# mcu.net
KiCad netlist of a schematic drawn in Altium Designer
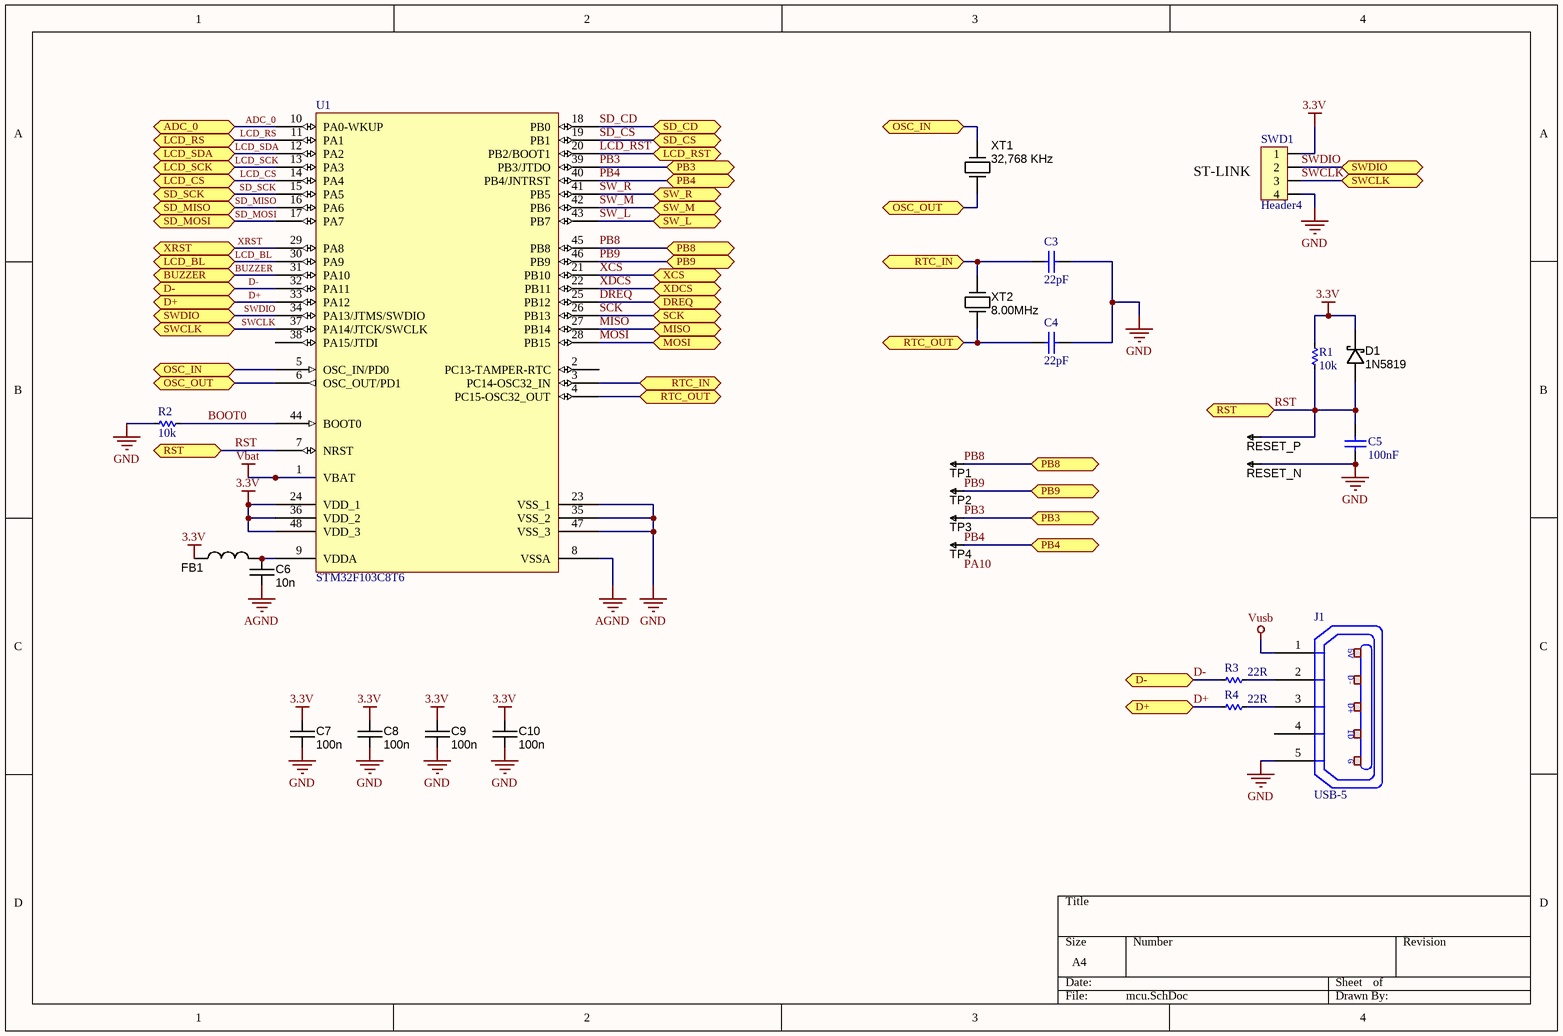
[diagram p0: mcu.SchDoc]

(export (version "E")
  (design (tool "Eeschema 10.0.6"))
  (components
    (comp (ref "C3")
      (value "22pF")
      (footprint "C0805")
      (description "Capacitor (Semiconductor SIM Model)")
      (fields (field (name "Comment") "Cap Semi") (field (name "PUBLISHER") "Altium Limited"))
      (libsource (lib "Mylib") (part "Cap Semi"))
    )
    (comp (ref "C4")
      (value "22pF")
      (footprint "C0805")
      (description "Capacitor (Semiconductor SIM Model)")
      (fields (field (name "Comment") "Cap Semi") (field (name "PUBLISHER") "Altium Limited"))
      (libsource (lib "Mylib") (part "Cap Semi"))
    )
    (comp (ref "C5")
      (value "100nF")
      (footprint "C0805")
      (description "Capacitor (Semiconductor SIM Model)")
      (fields (field (name "Comment") "Cap Semi") (field (name "PUBLISHER") "Altium Limited"))
      (libsource (lib "Mylib") (part "Cap Semi"))
    )
    (comp (ref "C6")
      (value "10n")
      (footprint "CAPC1608X90N")
      (description "Capacitor SMD Cer 100nF 10% 50V X7R 0603")
      (fields (field (name "TOLERANCE") "±10%") (field (name "Comment") "approved sub OK"))
      (libsource (lib "PBL - Capacitors") (part "CAPC_100n_0603_X7R_50V_10%"))
    )
    (comp (ref "C7")
      (value "100n")
      (footprint "CAPC1608X90N")
      (description "Capacitor SMD Cer 100nF 10% 50V X7R 0603")
      (fields (field (name "TOLERANCE") "±10%") (field (name "Comment") "approved sub OK"))
      (libsource (lib "PBL - Capacitors") (part "CAPC_100n_0603_X7R_50V_10%"))
    )
    (comp (ref "C8")
      (value "100n")
      (footprint "CAPC1608X90N")
      (description "Capacitor SMD Cer 100nF 10% 50V X7R 0603")
      (fields (field (name "TOLERANCE") "±10%") (field (name "Comment") "approved sub OK"))
      (libsource (lib "PBL - Capacitors") (part "CAPC_100n_0603_X7R_50V_10%"))
    )
    (comp (ref "C9")
      (value "100n")
      (footprint "CAPC1608X90N")
      (description "Capacitor SMD Cer 100nF 10% 50V X7R 0603")
      (fields (field (name "TOLERANCE") "±10%") (field (name "Comment") "approved sub OK"))
      (libsource (lib "PBL - Capacitors") (part "CAPC_100n_0603_X7R_50V_10%"))
    )
    (comp (ref "C10")
      (value "100n")
      (footprint "CAPC1608X90N")
      (description "Capacitor SMD Cer 100nF 10% 50V X7R 0603")
      (fields (field (name "TOLERANCE") "±10%") (field (name "Comment") "approved sub OK"))
      (libsource (lib "PBL - Capacitors") (part "CAPC_100n_0603_X7R_50V_10%"))
    )
    (comp (ref "D1")
      (value "DIODE_SCHOTTKY_40V_1A")
      (footprint "SOD123")
      (description "Diode Schottky SMD 40V 1A SOD123")
      (fields (field (name "MANUFACTURER PART NUMBER 1") "1N5819"))
      (libsource (lib "PBL - Diodes") (part "DIODE_SCHOTTKY_40V_1A"))
    )
    (comp (ref "FB1")
      (value "2K2 @ 100 MHz")
      (footprint "FBC2012N")
      (description "Ferrite bead 2.2K Ohm at 100 MHz 200mA 0805 SMD")
      (libsource (lib "PBL - Inductors") (part "FERRITE_2K2-100MHz_0805"))
    )
    (comp (ref "J1")
      (value "USB-5")
      (footprint "USB-M1")
      (fields
        (field (name "MANUFACTURER") "FCI")
        (field (name "MANUFACTURER PART NUMBER") "10118193-0001LF")
        (field (name ".CREATOR") "MM")
        (field (name ".CHECKED PCB") "RF")
        (field (name ".CHECKED SCH") "MM")
      )
      (libsource (lib "LIBRARY") (part "USB-5"))
    )
    (comp (ref "R1")
      (value "10k")
      (footprint "RES-SMD-0805")
      (description "Resistor")
      (fields
        (field (name "MANUFACTURER") "Generic Components")
        (field (name "Comment") "Res")
        (field (name "PUBLISHER") "Altium Hobart Technology Centre")
      )
      (libsource (lib "Mylib") (part "Res-SMD"))
    )
    (comp (ref "R2")
      (value "10k")
      (footprint "RES-SMD-0603")
      (description "Resistor")
      (fields
        (field (name "MANUFACTURER") "Generic Components")
        (field (name "Comment") "Res")
        (field (name "PUBLISHER") "Altium Hobart Technology Centre")
      )
      (libsource (lib "Mylib") (part "Res-SMD"))
    )
    (comp (ref "R3")
      (value "22R")
      (footprint "RES-SMD-0603")
      (description "Resistor")
      (fields
        (field (name "MANUFACTURER") "Generic Components")
        (field (name "Comment") "Res")
        (field (name "PUBLISHER") "Altium Hobart Technology Centre")
      )
      (libsource (lib "Mylib") (part "Res-SMD"))
    )
    (comp (ref "R4")
      (value "22R")
      (footprint "RES-SMD-0603")
      (description "Resistor")
      (fields
        (field (name "MANUFACTURER") "Generic Components")
        (field (name "Comment") "Res")
        (field (name "PUBLISHER") "Altium Hobart Technology Centre")
      )
      (libsource (lib "Mylib") (part "Res-SMD"))
    )
    (comp (ref "RESET_N")
      (value "TESTPOINT")
      (footprint "TP-R60")
      (description "SMD test pin")
      (libsource (lib "PBL - Test Points") (part "TESTPOINT"))
    )
    (comp (ref "RESET_P")
      (value "TESTPOINT")
      (footprint "TP-R60")
      (description "SMD test pin")
      (libsource (lib "PBL - Test Points") (part "TESTPOINT"))
    )
    (comp (ref "SWD1")
      (value "Header4")
      (footprint "HDR4")
      (description "Header IDC, 4 x 1 Pin Vertical 2.54mm Pitch (Non-Boxed, Male)")
      (fields
        (field (name "MANUFACTURER") "Würth Elektronik eiSos GmbH")
        (field (name "PARTNO") "613002143121")
        (field (name "CREATED BY") "Karrer Zheng")
      )
      (libsource (lib "LIBRARY") (part "Header4"))
    )
    (comp (ref "TP1")
      (value "TESTPOINT")
      (footprint "TP-R60")
      (description "SMD test pin")
      (libsource (lib "PBL - Test Points") (part "TESTPOINT"))
    )
    (comp (ref "TP2")
      (value "TESTPOINT")
      (footprint "TP-R60")
      (description "SMD test pin")
      (libsource (lib "PBL - Test Points") (part "TESTPOINT"))
    )
    (comp (ref "TP3")
      (value "TESTPOINT")
      (footprint "TP-R60")
      (description "SMD test pin")
      (libsource (lib "PBL - Test Points") (part "TESTPOINT"))
    )
    (comp (ref "TP4")
      (value "TESTPOINT")
      (footprint "TP-R60")
      (description "SMD test pin")
      (libsource (lib "PBL - Test Points") (part "TESTPOINT"))
    )
    (comp (ref "U1")
      (value "STM32F103C8T6")
      (footprint "LQFP48_N")
      (description "STM32 ARM-based 32-bit MCU with 64 Kbytes Flash, 48-pin LQFP, Industrial Temperature")
      (fields (field (name "PUBLISHER") "Altium Limited"))
      (libsource (lib "ST Microcontroller 32-Bit STM32") (part "STM32F103C8T6"))
    )
    (comp (ref "XT1")
      (value "32,768 KHz")
      (footprint "CRYSTAL_CMR309T")
      (description "Resonator Ceramic 6.00 MHz 30ppm")
      (fields (field (name "TOLERANCE") "±50ppm"))
      (libsource (lib "PBL - Resonators") (part "Crystal_6MHz_CMR309T"))
    )
    (comp (ref "XT2")
      (value "8.00MHz")
      (footprint "CRYSTAL_HC49-US-SM")
      (description "Resonator Ceramic 6.00 MHz 30ppm")
      (libsource (lib "PBL - Resonators") (part "Crystal_6MHz_HC49/US"))
    )
  )
  (nets
    (net (code "1") (name "/ADC_0") (class "Default")
      (node (ref "U1") (pin "10") (pinfunction "PA0-WKUP_10") (pintype "bidirectional"))
    )
    (net (code "2") (name "/BOOT0") (class "Default")
      (node (ref "R2") (pin "1") (pinfunction "1_1") (pintype "passive"))
      (node (ref "U1") (pin "44") (pinfunction "BOOT0_44") (pintype "input"))
    )
    (net (code "3") (name "/BUZZER") (class "Default")
      (node (ref "U1") (pin "31") (pinfunction "PA10_31") (pintype "bidirectional"))
    )
    (net (code "4") (name "/D+") (class "Default")
      (node (ref "R4") (pin "2") (pinfunction "2_2") (pintype "passive"))
      (node (ref "U1") (pin "33") (pinfunction "PA12_33") (pintype "bidirectional"))
    )
    (net (code "5") (name "/D-") (class "Default")
      (node (ref "R3") (pin "2") (pinfunction "2_2") (pintype "passive"))
      (node (ref "U1") (pin "32") (pinfunction "PA11_32") (pintype "bidirectional"))
    )
    (net (code "6") (name "/DREQ") (class "Default")
      (node (ref "U1") (pin "25") (pinfunction "PB12_25") (pintype "bidirectional"))
    )
    (net (code "7") (name "/LCD_BL") (class "Default")
      (node (ref "U1") (pin "30") (pinfunction "PA9_30") (pintype "bidirectional"))
    )
    (net (code "8") (name "/LCD_CS") (class "Default")
      (node (ref "U1") (pin "14") (pinfunction "PA4_14") (pintype "bidirectional"))
    )
    (net (code "9") (name "/LCD_RS") (class "Default")
      (node (ref "U1") (pin "11") (pinfunction "PA1_11") (pintype "bidirectional"))
    )
    (net (code "10") (name "/LCD_RST") (class "Default")
      (node (ref "U1") (pin "20") (pinfunction "PB2/BOOT1_20") (pintype "bidirectional"))
    )
    (net (code "11") (name "/LCD_SCK") (class "Default")
      (node (ref "U1") (pin "13") (pinfunction "PA3_13") (pintype "bidirectional"))
    )
    (net (code "12") (name "/LCD_SDA") (class "Default")
      (node (ref "U1") (pin "12") (pinfunction "PA2_12") (pintype "bidirectional"))
    )
    (net (code "13") (name "/MISO") (class "Default")
      (node (ref "U1") (pin "27") (pinfunction "PB14_27") (pintype "bidirectional"))
    )
    (net (code "14") (name "/MOSI") (class "Default")
      (node (ref "U1") (pin "28") (pinfunction "PB15_28") (pintype "bidirectional"))
    )
    (net (code "15") (name "/OSC_IN") (class "Default")
      (node (ref "U1") (pin "5") (pinfunction "OSC_IN/PD0_5") (pintype "input"))
      (node (ref "XT1") (pin "2") (pinfunction "OUT_2") (pintype "passive"))
    )
    (net (code "16") (name "/OSC_OUT") (class "Default")
      (node (ref "U1") (pin "6") (pinfunction "OSC_OUT/PD1_6") (pintype "output"))
      (node (ref "XT1") (pin "1") (pinfunction "IN_1") (pintype "passive"))
    )
    (net (code "18") (name "/PB3") (class "Default")
      (node (ref "TP3") (pin "1") (pintype "passive"))
      (node (ref "U1") (pin "39") (pinfunction "PB3/JTDO_39") (pintype "bidirectional"))
    )
    (net (code "19") (name "/PB4") (class "Default")
      (node (ref "TP4") (pin "1") (pintype "passive"))
      (node (ref "U1") (pin "40") (pinfunction "PB4/JNTRST_40") (pintype "bidirectional"))
    )
    (net (code "20") (name "/PB8") (class "Default")
      (node (ref "TP1") (pin "1") (pintype "passive"))
      (node (ref "U1") (pin "45") (pinfunction "PB8_45") (pintype "bidirectional"))
    )
    (net (code "21") (name "/PB9") (class "Default")
      (node (ref "TP2") (pin "1") (pintype "passive"))
      (node (ref "U1") (pin "46") (pinfunction "PB9_46") (pintype "bidirectional"))
    )
    (net (code "22") (name "/RST") (class "Default")
      (node (ref "C5") (pin "2") (pinfunction "2_2") (pintype "passive"))
      (node (ref "D1") (pin "A") (pinfunction "A_A") (pintype "passive"))
      (node (ref "R1") (pin "2") (pinfunction "2_2") (pintype "passive"))
      (node (ref "RESET_P") (pin "1") (pintype "passive"))
      (node (ref "U1") (pin "7") (pinfunction "NRST_7") (pintype "bidirectional"))
    )
    (net (code "23") (name "/RTC_IN") (class "Default")
      (node (ref "C3") (pin "2") (pinfunction "2_2") (pintype "passive"))
      (node (ref "U1") (pin "3") (pinfunction "PC14-OSC32_IN_3") (pintype "bidirectional"))
      (node (ref "XT2") (pin "2") (pinfunction "OUT_2") (pintype "passive"))
    )
    (net (code "24") (name "/RTC_OUT") (class "Default")
      (node (ref "C4") (pin "2") (pinfunction "2_2") (pintype "passive"))
      (node (ref "U1") (pin "4") (pinfunction "PC15-OSC32_OUT_4") (pintype "bidirectional"))
      (node (ref "XT2") (pin "1") (pinfunction "IN_1") (pintype "passive"))
    )
    (net (code "25") (name "/SCK") (class "Default")
      (node (ref "U1") (pin "26") (pinfunction "PB13_26") (pintype "bidirectional"))
    )
    (net (code "26") (name "/SD_CD") (class "Default")
      (node (ref "U1") (pin "18") (pinfunction "PB0_18") (pintype "bidirectional"))
    )
    (net (code "27") (name "/SD_CS") (class "Default")
      (node (ref "U1") (pin "19") (pinfunction "PB1_19") (pintype "bidirectional"))
    )
    (net (code "28") (name "/SD_MISO") (class "Default")
      (node (ref "U1") (pin "16") (pinfunction "PA6_16") (pintype "bidirectional"))
    )
    (net (code "29") (name "/SD_MOSI") (class "Default")
      (node (ref "U1") (pin "17") (pinfunction "PA7_17") (pintype "bidirectional"))
    )
    (net (code "30") (name "/SD_SCK") (class "Default")
      (node (ref "U1") (pin "15") (pinfunction "PA5_15") (pintype "bidirectional"))
    )
    (net (code "31") (name "/SWCLK") (class "Default")
      (node (ref "SWD1") (pin "3") (pinfunction "3_3") (pintype "passive"))
      (node (ref "U1") (pin "37") (pinfunction "PA14/JTCK/SWCLK_37") (pintype "bidirectional"))
    )
    (net (code "32") (name "/SWDIO") (class "Default")
      (node (ref "SWD1") (pin "2") (pinfunction "2_2") (pintype "passive"))
      (node (ref "U1") (pin "34") (pinfunction "PA13/JTMS/SWDIO_34") (pintype "bidirectional"))
    )
    (net (code "33") (name "/SW_L") (class "Default")
      (node (ref "U1") (pin "43") (pinfunction "PB7_43") (pintype "bidirectional"))
    )
    (net (code "34") (name "/SW_M") (class "Default")
      (node (ref "U1") (pin "42") (pinfunction "PB6_42") (pintype "bidirectional"))
    )
    (net (code "35") (name "/SW_R") (class "Default")
      (node (ref "U1") (pin "41") (pinfunction "PB5_41") (pintype "bidirectional"))
    )
    (net (code "36") (name "/XCS") (class "Default")
      (node (ref "U1") (pin "21") (pinfunction "PB10_21") (pintype "bidirectional"))
    )
    (net (code "37") (name "/XDCS") (class "Default")
      (node (ref "U1") (pin "22") (pinfunction "PB11_22") (pintype "bidirectional"))
    )
    (net (code "38") (name "/XRST") (class "Default")
      (node (ref "U1") (pin "29") (pinfunction "PA8_29") (pintype "bidirectional"))
    )
    (net (code "39") (name "3.3V") (class "Default")
      (node (ref "C10") (pin "1") (pintype "passive"))
      (node (ref "C7") (pin "1") (pintype "passive"))
      (node (ref "C8") (pin "1") (pintype "passive"))
      (node (ref "C9") (pin "1") (pintype "passive"))
      (node (ref "D1") (pin "K") (pinfunction "K_K") (pintype "passive"))
      (node (ref "FB1") (pin "1") (pinfunction "1_1") (pintype "passive"))
      (node (ref "R1") (pin "1") (pinfunction "1_1") (pintype "passive"))
      (node (ref "SWD1") (pin "1") (pinfunction "1_1") (pintype "passive"))
      (node (ref "U1") (pin "24") (pinfunction "VDD_1_24") (pintype "power_in"))
      (node (ref "U1") (pin "36") (pinfunction "VDD_2_36") (pintype "power_in"))
      (node (ref "U1") (pin "48") (pinfunction "VDD_3_48") (pintype "power_in"))
    )
    (net (code "40") (name "AGND") (class "Default")
      (node (ref "C6") (pin "2") (pintype "passive"))
      (node (ref "U1") (pin "8") (pinfunction "VSSA_8") (pintype "power_in"))
    )
    (net (code "41") (name "GND") (class "Default")
      (node (ref "C10") (pin "2") (pintype "passive"))
      (node (ref "C3") (pin "1") (pinfunction "1_1") (pintype "passive"))
      (node (ref "C4") (pin "1") (pinfunction "1_1") (pintype "passive"))
      (node (ref "C5") (pin "1") (pinfunction "1_1") (pintype "passive"))
      (node (ref "C7") (pin "2") (pintype "passive"))
      (node (ref "C8") (pin "2") (pintype "passive"))
      (node (ref "C9") (pin "2") (pintype "passive"))
      (node (ref "J1") (pin "5") (pinfunction "P5_5") (pintype "passive"))
      (node (ref "R2") (pin "2") (pinfunction "2_2") (pintype "passive"))
      (node (ref "RESET_N") (pin "1") (pintype "passive"))
      (node (ref "SWD1") (pin "4") (pinfunction "4_4") (pintype "passive"))
      (node (ref "U1") (pin "23") (pinfunction "VSS_1_23") (pintype "power_in"))
      (node (ref "U1") (pin "35") (pinfunction "VSS_2_35") (pintype "power_in"))
      (node (ref "U1") (pin "47") (pinfunction "VSS_3_47") (pintype "power_in"))
    )
    (net (code "42") (name "Net-(J1-P2)") (class "Default")
      (node (ref "J1") (pin "2") (pinfunction "P2_2") (pintype "passive"))
      (node (ref "R3") (pin "1") (pinfunction "1_1") (pintype "passive"))
    )
    (net (code "43") (name "Net-(J1-P3)") (class "Default")
      (node (ref "J1") (pin "3") (pinfunction "P3_3") (pintype "passive"))
      (node (ref "R4") (pin "1") (pinfunction "1_1") (pintype "passive"))
    )
    (net (code "44") (name "Net-(U1-VDDA)") (class "Default")
      (node (ref "C6") (pin "1") (pintype "passive"))
      (node (ref "FB1") (pin "2") (pinfunction "2_2") (pintype "passive"))
      (node (ref "U1") (pin "9") (pinfunction "VDDA_9") (pintype "power_in"))
    )
    (net (code "45") (name "Vbat") (class "Default")
      (node (ref "U1") (pin "1") (pinfunction "VBAT_1") (pintype "power_in"))
    )
    (net (code "46") (name "Vusb") (class "Default")
      (node (ref "J1") (pin "1") (pinfunction "P1_1") (pintype "passive"))
    )
    (net (code "47") (name "unconnected-(J1-P4-Pad4)") (class "Default")
      (node (ref "J1") (pin "4") (pinfunction "P4_4") (pintype "passive"))
    )
    (net (code "48") (name "unconnected-(U1-PA15{slash}JTDI-Pad38)") (class "Default")
      (node (ref "U1") (pin "38") (pinfunction "PA15/JTDI_38") (pintype "bidirectional"))
    )
    (net (code "49") (name "unconnected-(U1-PC13-TAMPER-RTC-Pad2)") (class "Default")
      (node (ref "U1") (pin "2") (pinfunction "PC13-TAMPER-RTC_2") (pintype "bidirectional"))
    )
  )
)
